# CENTRALE02c3.net
KiCad netlist of a schematic drawn in EAGLE
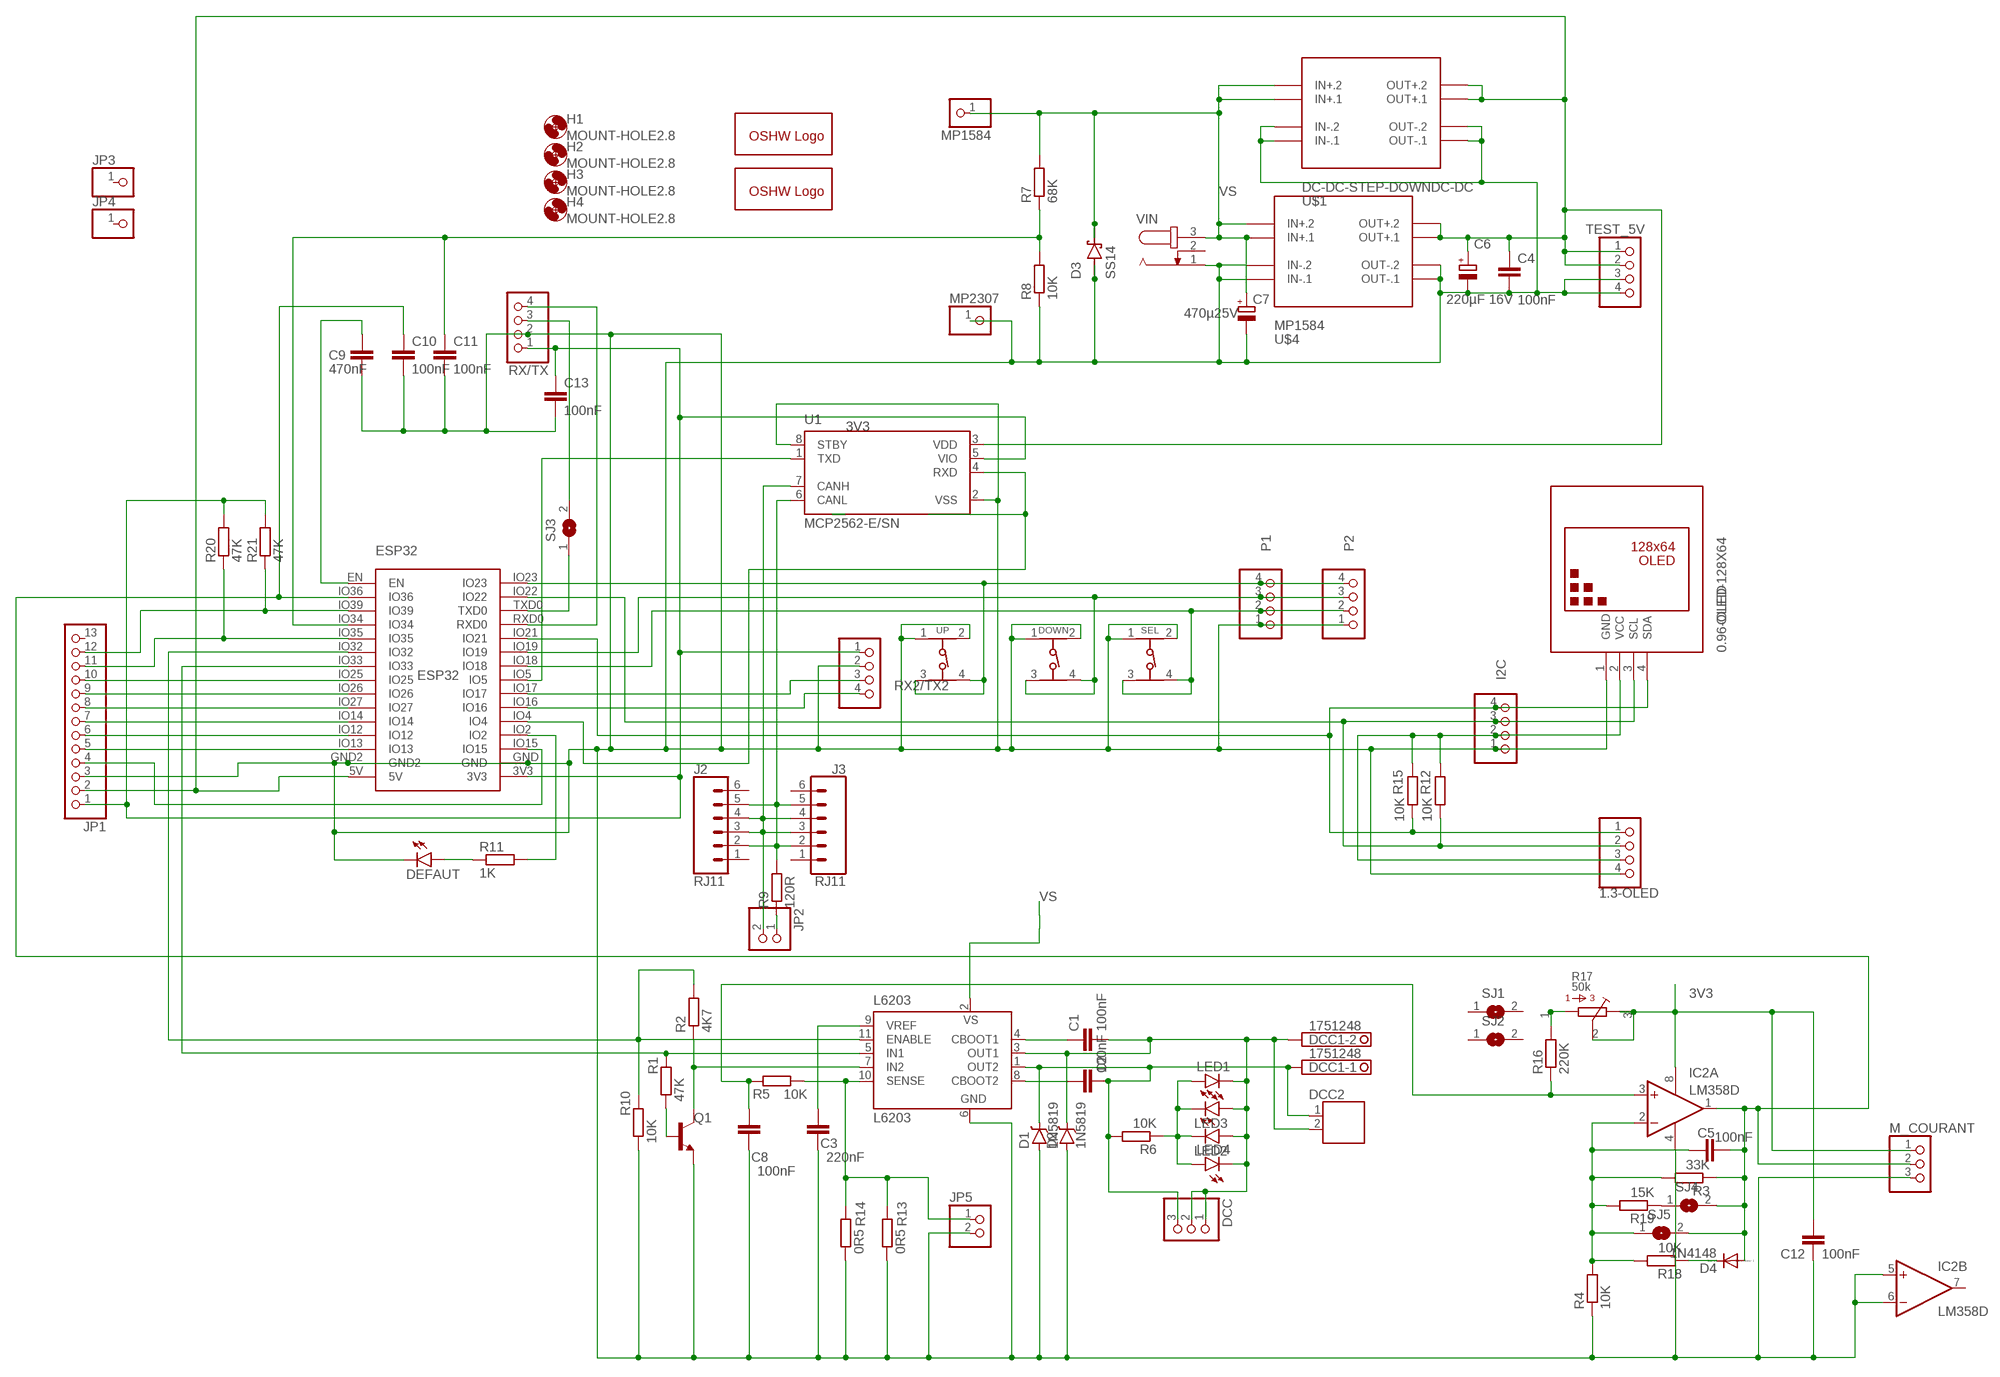
[diagram p0: schematic, sheet 1]

(export (version "E")
  (design (tool "Eeschema 10.0.6"))
  (components
    (comp (ref "0.96-OLED")
      (value "OLED-128X64")
      (footprint "eagle-import:DISPLAY-OLED-128X64-I2C")
      (libsource (lib "eagle-import") (part "DISPLAY-OLED-128X64-I2C"))
    )
    (comp (ref "1.3-OLED")
      (value "PINHD-1X4")
      (footprint "eagle-import:1X04")
      (libsource (lib "eagle-import") (part "PINHD-1X4"))
    )
    (comp (ref "C1")
      (value "100nF")
      (footprint "eagle-import:C1206")
      (libsource (lib "eagle-import") (part "C-EUC1206"))
    )
    (comp (ref "C2")
      (value "100nF")
      (footprint "eagle-import:C1206")
      (libsource (lib "eagle-import") (part "C-EUC1206"))
    )
    (comp (ref "C3")
      (value "220nF")
      (footprint "eagle-import:C1206")
      (libsource (lib "eagle-import") (part "C-EUC1206"))
    )
    (comp (ref "C4")
      (value "100nF")
      (footprint "eagle-import:C1206")
      (libsource (lib "eagle-import") (part "C-EUC1206"))
    )
    (comp (ref "C5")
      (value "100nF")
      (footprint "eagle-import:C1206")
      (libsource (lib "eagle-import") (part "C-EUC1206"))
    )
    (comp (ref "C6")
      (value "220µF 16V")
      (footprint "eagle-import:E2,5-7")
      (libsource (lib "eagle-import") (part "CPOL-EUE2.5-7"))
    )
    (comp (ref "C7")
      (value "470µ25V")
      (footprint "eagle-import:E5-10,5")
      (libsource (lib "eagle-import") (part "CPOL-EUE5-10.5"))
    )
    (comp (ref "C8")
      (value "100nF")
      (footprint "eagle-import:C1206")
      (libsource (lib "eagle-import") (part "C-EUC1206"))
    )
    (comp (ref "C9")
      (value "470nF")
      (footprint "eagle-import:C1206")
      (libsource (lib "eagle-import") (part "C-EUC1206"))
    )
    (comp (ref "C10")
      (value "100nF")
      (footprint "eagle-import:C1206")
      (libsource (lib "eagle-import") (part "C-EUC1206"))
    )
    (comp (ref "C11")
      (value "100nF")
      (footprint "eagle-import:C1206")
      (libsource (lib "eagle-import") (part "C-EUC1206"))
    )
    (comp (ref "C12")
      (value "100nF")
      (footprint "eagle-import:C1206")
      (libsource (lib "eagle-import") (part "C-EUC1206"))
    )
    (comp (ref "C13")
      (value "100nF")
      (footprint "eagle-import:C1206")
      (libsource (lib "eagle-import") (part "C-EUC1206"))
    )
    (comp (ref "D1")
      (value "1N5819")
      (footprint "eagle-import:SMA-DIODE")
      (fields (field (name "MF") "ON Semiconductor") (field (name "MP") "MBRA140"))
      (libsource (lib "eagle-import") (part "MBRA140"))
    )
    (comp (ref "D2")
      (value "1N5819")
      (footprint "eagle-import:SMA-DIODE")
      (fields (field (name "MF") "ON Semiconductor") (field (name "MP") "MBRA140"))
      (libsource (lib "eagle-import") (part "MBRA140"))
    )
    (comp (ref "D3")
      (value "SS14")
      (footprint "eagle-import:DIOM4325X250N")
      (fields (field (name "MF") "Taiwan Semiconductor"))
      (libsource (lib "eagle-import") (part "SS14"))
    )
    (comp (ref "D4")
      (value "1N4148")
      (footprint "eagle-import:DO35-7")
      (libsource (lib "eagle-import") (part "1N4148DO35-7"))
    )
    (comp (ref "DCC")
      (value "PINHD-1X3")
      (footprint "eagle-import:1X03")
      (libsource (lib "eagle-import") (part "PINHD-1X3"))
    )
    (comp (ref "DCC1")
      (value "1751248")
      (footprint "eagle-import:1751248")
      (libsource (lib "eagle-import") (part "1751248"))
    )
    (comp (ref "DCC2")
      (value "691502710002")
      (footprint "eagle-import:691502710002")
      (libsource (lib "eagle-import") (part "691502710002"))
    )
    (comp (ref "DEFAUT")
      (value "LEDSMT1206")
      (footprint "eagle-import:1206")
      (libsource (lib "eagle-import") (part "LEDSMT1206"))
    )
    (comp (ref "DOWN")
      (value "430456073736")
      (footprint "eagle-import:4304X60737X6")
      (libsource (lib "eagle-import") (part "430456073736"))
    )
    (comp (ref "ESP32")
      (value "ESP32")
      (footprint "eagle-import:ESP32")
      (fields (field (name "MF") "Texas Instruments") (field (name "MP") "SN754410"))
      (libsource (lib "eagle-import") (part "ESP32"))
    )
    (comp (ref "GOLD_ORB_SM1")
      (value "OSHWLOGOLOGO5MM")
      (footprint "eagle-import:OSHW_5MM")
      (libsource (lib "eagle-import") (part "OSHWLOGOLOGO5MM"))
    )
    (comp (ref "GOLD_ORB_SM2")
      (value "OSHWLOGOLOGO5MM")
      (footprint "eagle-import:OSHW_5MM")
      (libsource (lib "eagle-import") (part "OSHWLOGOLOGO5MM"))
    )
    (comp (ref "H1")
      (value "MOUNT-HOLE2.8")
      (footprint "eagle-import:2,8")
      (libsource (lib "eagle-import") (part "MOUNT-HOLE2.8"))
    )
    (comp (ref "H2")
      (value "MOUNT-HOLE2.8")
      (footprint "eagle-import:2,8")
      (libsource (lib "eagle-import") (part "MOUNT-HOLE2.8"))
    )
    (comp (ref "H3")
      (value "MOUNT-HOLE2.8")
      (footprint "eagle-import:2,8")
      (libsource (lib "eagle-import") (part "MOUNT-HOLE2.8"))
    )
    (comp (ref "H4")
      (value "MOUNT-HOLE2.8")
      (footprint "eagle-import:2,8")
      (libsource (lib "eagle-import") (part "MOUNT-HOLE2.8"))
    )
    (comp (ref "I2C")
      (value "PINHD-1X4")
      (footprint "eagle-import:1X04")
      (libsource (lib "eagle-import") (part "PINHD-1X4"))
    )
    (comp (ref "IC2")
      (value "LM358D")
      (footprint "eagle-import:SO08")
      (libsource (lib "eagle-import") (part "LM358D"))
    )
    (comp (ref "J2")
      (value "RJ11")
      (footprint "eagle-import:RJ11-6")
      (libsource (lib "eagle-import") (part "RJ11-6"))
    )
    (comp (ref "J3")
      (value "RJ11")
      (footprint "eagle-import:RJ11-6")
      (libsource (lib "eagle-import") (part "RJ11-6"))
    )
    (comp (ref "JP1")
      (value "PINHD-1X13")
      (footprint "eagle-import:1X13")
      (libsource (lib "eagle-import") (part "PINHD-1X13"))
    )
    (comp (ref "JP2")
      (value "PINHD-1X2")
      (footprint "eagle-import:1X02")
      (libsource (lib "eagle-import") (part "PINHD-1X2"))
    )
    (comp (ref "JP3")
      (value "PINHD-1X1")
      (footprint "eagle-import:1X01")
      (libsource (lib "eagle-import") (part "PINHD-1X1"))
    )
    (comp (ref "JP4")
      (value "PINHD-1X1")
      (footprint "eagle-import:1X01")
      (libsource (lib "eagle-import") (part "PINHD-1X1"))
    )
    (comp (ref "JP5")
      (value "PINHD-1X2")
      (footprint "eagle-import:1X02")
      (libsource (lib "eagle-import") (part "PINHD-1X2"))
    )
    (comp (ref "L6203")
      (value "L6203")
      (footprint "eagle-import:MULTIWATT-11")
      (libsource (lib "eagle-import") (part "L6203"))
    )
    (comp (ref "LED1")
      (value "LEDSMT1206")
      (footprint "eagle-import:1206")
      (libsource (lib "eagle-import") (part "LEDSMT1206"))
    )
    (comp (ref "LED2")
      (value "LED3MM")
      (footprint "eagle-import:LED3MM")
      (libsource (lib "eagle-import") (part "LED3MM"))
    )
    (comp (ref "LED3")
      (value "LEDSMT1206")
      (footprint "eagle-import:1206")
      (libsource (lib "eagle-import") (part "LEDSMT1206"))
    )
    (comp (ref "LED4")
      (value "LED3MM")
      (footprint "eagle-import:LED3MM")
      (libsource (lib "eagle-import") (part "LED3MM"))
    )
    (comp (ref "MP1584")
      (value "PINHD-1X1")
      (footprint "eagle-import:1X01")
      (libsource (lib "eagle-import") (part "pinhead_325_PINHD-1X1"))
    )
    (comp (ref "MP2307")
      (value "PINHD-1X1")
      (footprint "eagle-import:1X01")
      (libsource (lib "eagle-import") (part "pinhead_325_PINHD-1X1"))
    )
    (comp (ref "M_COURANT")
      (value "PINHD-1X3")
      (footprint "eagle-import:1X03")
      (libsource (lib "eagle-import") (part "PINHD-1X3"))
    )
    (comp (ref "P1")
      (value "PINHD-1X4")
      (footprint "eagle-import:1X04")
      (libsource (lib "eagle-import") (part "PINHD-1X4"))
    )
    (comp (ref "P2")
      (value "PINHD-1X4")
      (footprint "eagle-import:1X04")
      (libsource (lib "eagle-import") (part "PINHD-1X4"))
    )
    (comp (ref "Q1")
      (value "MMBT3904LT1-NPN-SOT23-BEC")
      (footprint "eagle-import:SOT23-BEC")
      (libsource (lib "eagle-import") (part "-NPN-SOT23-BECMMBT3904LT1"))
    )
    (comp (ref "R1")
      (value "47K")
      (footprint "eagle-import:R0805")
      (libsource (lib "eagle-import") (part "R-EU_R0805"))
    )
    (comp (ref "R2")
      (value "4K7")
      (footprint "eagle-import:R0805")
      (libsource (lib "eagle-import") (part "R-EU_R0805"))
    )
    (comp (ref "R3")
      (value "33K")
      (footprint "eagle-import:R0805")
      (libsource (lib "eagle-import") (part "R-EU_R0805"))
    )
    (comp (ref "R4")
      (value "10K")
      (footprint "eagle-import:R0805")
      (libsource (lib "eagle-import") (part "R-EU_R0805"))
    )
    (comp (ref "R5")
      (value "10K")
      (footprint "eagle-import:R0805")
      (libsource (lib "eagle-import") (part "R-EU_R0805"))
    )
    (comp (ref "R6")
      (value "10K")
      (footprint "eagle-import:R0805")
      (libsource (lib "eagle-import") (part "R-EU_R0805"))
    )
    (comp (ref "R7")
      (value "68K")
      (footprint "eagle-import:R0805")
      (libsource (lib "eagle-import") (part "R-EU_R0805"))
    )
    (comp (ref "R8")
      (value "10K")
      (footprint "eagle-import:R0805")
      (libsource (lib "eagle-import") (part "R-EU_R0805"))
    )
    (comp (ref "R9")
      (value "120R")
      (footprint "eagle-import:M1206")
      (libsource (lib "eagle-import") (part "resistor_348_R-EU_M1206"))
    )
    (comp (ref "R10")
      (value "10K")
      (footprint "eagle-import:R0805")
      (libsource (lib "eagle-import") (part "R-EU_R0805"))
    )
    (comp (ref "R11")
      (value "1K")
      (footprint "eagle-import:R0805")
      (libsource (lib "eagle-import") (part "R-EU_R0805"))
    )
    (comp (ref "R12")
      (value "10K")
      (footprint "eagle-import:R0805")
      (libsource (lib "eagle-import") (part "R-EU_R0805"))
    )
    (comp (ref "R13")
      (value "0R5")
      (footprint "eagle-import:R2512")
      (libsource (lib "eagle-import") (part "R-EU_R2512"))
    )
    (comp (ref "R14")
      (value "0R5")
      (footprint "eagle-import:R2512")
      (libsource (lib "eagle-import") (part "R-EU_R2512"))
    )
    (comp (ref "R15")
      (value "10K")
      (footprint "eagle-import:R0805")
      (libsource (lib "eagle-import") (part "R-EU_R0805"))
    )
    (comp (ref "R16")
      (value "220K")
      (footprint "eagle-import:R0805")
      (libsource (lib "eagle-import") (part "R-EU_R0805"))
    )
    (comp (ref "R17")
      (value "50k")
      (footprint "eagle-import:3386-MULTI")
      (libsource (lib "eagle-import") (part "3386"))
    )
    (comp (ref "R18")
      (value "10K")
      (footprint "eagle-import:R0805")
      (libsource (lib "eagle-import") (part "R-EU_R0805"))
    )
    (comp (ref "R19")
      (value "15K")
      (footprint "eagle-import:R0805")
      (libsource (lib "eagle-import") (part "R-EU_R0805"))
    )
    (comp (ref "R20")
      (value "47K")
      (footprint "eagle-import:R0805")
      (libsource (lib "eagle-import") (part "R-EU_R0805"))
    )
    (comp (ref "R21")
      (value "47K")
      (footprint "eagle-import:R0805")
      (libsource (lib "eagle-import") (part "R-EU_R0805"))
    )
    (comp (ref "RX/TX")
      (value "PINHD-1X4")
      (footprint "eagle-import:1X04")
      (libsource (lib "eagle-import") (part "PINHD-1X4"))
    )
    (comp (ref "RX2/TX2")
      (value "PINHD-1X4")
      (footprint "eagle-import:1X04")
      (libsource (lib "eagle-import") (part "PINHD-1X4"))
    )
    (comp (ref "SEL")
      (value "430456073736")
      (footprint "eagle-import:4304X60737X6")
      (libsource (lib "eagle-import") (part "430456073736"))
    )
    (comp (ref "SJ1") (value "SJ") (footprint "eagle-import:SJ") (libsource (lib "eagle-import") (part "SJ")))
    (comp (ref "SJ2") (value "SJ") (footprint "eagle-import:SJ") (libsource (lib "eagle-import") (part "SJ")))
    (comp (ref "SJ3") (value "SJ") (footprint "eagle-import:SJ") (libsource (lib "eagle-import") (part "SJ")))
    (comp (ref "SJ4") (value "SJ") (footprint "eagle-import:SJ") (libsource (lib "eagle-import") (part "SJ")))
    (comp (ref "SJ5") (value "SJ") (footprint "eagle-import:SJ") (libsource (lib "eagle-import") (part "SJ")))
    (comp (ref "TEST_5V")
      (value "PINHD-1X4")
      (footprint "eagle-import:1X04")
      (libsource (lib "eagle-import") (part "PINHD-1X4"))
    )
    (comp (ref "U$1")
      (value "DC-DC-STEP-DOWNDC-DC")
      (footprint "eagle-import:DC-DC-STEP-DOWN")
      (libsource (lib "eagle-import") (part "DC-DC-STEP-DOWNDC-DC"))
    )
    (comp (ref "U$4")
      (value "MP1584")
      (footprint "eagle-import:DC-DC-STEP-DOWN-MP1584")
      (libsource (lib "eagle-import") (part "DC-DC-STEP-DOWN-MP1584"))
    )
    (comp (ref "U1")
      (value "MCP2562-E/SN")
      (footprint "eagle-import:SOIC127P600X175-8N")
      (fields (field (name "MF") "Microchip"))
      (libsource (lib "eagle-import") (part "MCP2562-E/SN"))
    )
    (comp (ref "UP")
      (value "430456073736")
      (footprint "eagle-import:4304X60737X6")
      (libsource (lib "eagle-import") (part "430456073736"))
    )
    (comp (ref "VIN")
      (value "JACK-PLUG0")
      (footprint "eagle-import:SPC4077")
      (libsource (lib "eagle-import") (part "JACK-PLUG0"))
    )
  )
  (nets
    (net (code "1") (name "/3V3") (class "Default")
      (node (ref "0.96-OLED") (pin "2") (pinfunction "VCC_2") (pintype "power_in"))
      (node (ref "1.3-OLED") (pin "3") (pinfunction "3_3") (pintype "passive"))
      (node (ref "C12") (pin "2") (pinfunction "2_2") (pintype "passive"))
      (node (ref "C13") (pin "2") (pinfunction "2_2") (pintype "passive"))
      (node (ref "ESP32") (pin "3V3") (pinfunction "3V3_3V3") (pintype "power_in"))
      (node (ref "I2C") (pin "2") (pinfunction "2_2") (pintype "passive"))
      (node (ref "IC2") (pin "8") (pinfunction "V+_8") (pintype "power_in"))
      (node (ref "JP1") (pin "1") (pinfunction "1_1") (pintype "passive"))
      (node (ref "M_COURANT") (pin "1") (pinfunction "1_1") (pintype "passive"))
      (node (ref "R12") (pin "1") (pinfunction "1_1") (pintype "passive"))
      (node (ref "R15") (pin "1") (pinfunction "1_1") (pintype "passive"))
      (node (ref "R17") (pin "2") (pinfunction "2_2") (pintype "passive"))
      (node (ref "R17") (pin "3") (pinfunction "3_3") (pintype "passive"))
      (node (ref "R17") (pin "6") (pinfunction "6_6") (pintype "passive"))
      (node (ref "R20") (pin "2") (pinfunction "2_2") (pintype "passive"))
      (node (ref "R21") (pin "2") (pinfunction "2_2") (pintype "passive"))
      (node (ref "RX/TX") (pin "1") (pinfunction "1_1") (pintype "passive"))
      (node (ref "RX2/TX2") (pin "1") (pinfunction "1_1") (pintype "passive"))
      (node (ref "U1") (pin "5") (pinfunction "VIO_5") (pintype "power_in"))
    )
    (net (code "2") (name "/VS") (class "Default")
      (node (ref "C7") (pin "+") (pinfunction "+_+") (pintype "passive"))
      (node (ref "D3") (pin "C") (pinfunction "K_C") (pintype "passive"))
      (node (ref "L6203") (pin "2") (pinfunction "VS_2") (pintype "power_in"))
      (node (ref "MP1584") (pin "1") (pinfunction "1_1") (pintype "passive"))
      (node (ref "R7") (pin "2") (pinfunction "2_2") (pintype "passive"))
      (node (ref "U$1") (pin "IN+.1") (pinfunction "IN+.1_IN+.1") (pintype "bidirectional"))
      (node (ref "U$1") (pin "IN+.2") (pinfunction "IN+.2_IN+.2") (pintype "bidirectional"))
      (node (ref "U$4") (pin "IN+.1") (pinfunction "IN+.1_IN+.1") (pintype "bidirectional"))
      (node (ref "U$4") (pin "IN+.2") (pinfunction "IN+.2_IN+.2") (pintype "bidirectional"))
      (node (ref "VIN") (pin "3") (pinfunction "3_3") (pintype "passive"))
    )
    (net (code "3") (name "Net-(0.96-OLED-GND)") (class "Default")
      (node (ref "0.96-OLED") (pin "1") (pinfunction "GND_1") (pintype "power_in"))
      (node (ref "1.3-OLED") (pin "4") (pinfunction "4_4") (pintype "passive"))
      (node (ref "C10") (pin "1") (pinfunction "1_1") (pintype "passive"))
      (node (ref "C11") (pin "1") (pinfunction "1_1") (pintype "passive"))
      (node (ref "C12") (pin "1") (pinfunction "1_1") (pintype "passive"))
      (node (ref "C13") (pin "1") (pinfunction "1_1") (pintype "passive"))
      (node (ref "C3") (pin "1") (pinfunction "1_1") (pintype "passive"))
      (node (ref "C4") (pin "2") (pinfunction "2_2") (pintype "passive"))
      (node (ref "C6") (pin "-") (pinfunction "-_-") (pintype "passive"))
      (node (ref "C7") (pin "-") (pinfunction "-_-") (pintype "passive"))
      (node (ref "C8") (pin "1") (pinfunction "1_1") (pintype "passive"))
      (node (ref "C9") (pin "2") (pinfunction "2_2") (pintype "passive"))
      (node (ref "D1") (pin "A") (pinfunction "A_A") (pintype "passive"))
      (node (ref "D2") (pin "A") (pinfunction "A_A") (pintype "passive"))
      (node (ref "D3") (pin "A") (pinfunction "A_A") (pintype "passive"))
      (node (ref "DEFAUT") (pin "C") (pinfunction "C_C") (pintype "passive"))
      (node (ref "DOWN") (pin "1") (pinfunction "1_1") (pintype "passive"))
      (node (ref "DOWN") (pin "2") (pinfunction "3_2") (pintype "passive"))
      (node (ref "ESP32") (pin "GND") (pinfunction "GND_GND") (pintype "power_in"))
      (node (ref "ESP32") (pin "GND2") (pinfunction "GND2_GND2") (pintype "power_in"))
      (node (ref "I2C") (pin "1") (pinfunction "1_1") (pintype "passive"))
      (node (ref "IC2") (pin "4") (pinfunction "V-_4") (pintype "power_in"))
      (node (ref "IC2") (pin "5") (pinfunction "+IN_5") (pintype "input"))
      (node (ref "IC2") (pin "6") (pinfunction "-IN_6") (pintype "input"))
      (node (ref "JP1") (pin "3") (pinfunction "3_3") (pintype "passive"))
      (node (ref "JP5") (pin "2") (pinfunction "2_2") (pintype "passive"))
      (node (ref "L6203") (pin "6") (pinfunction "GND_6") (pintype "power_in"))
      (node (ref "MP2307") (pin "1") (pinfunction "1_1") (pintype "passive"))
      (node (ref "M_COURANT") (pin "3") (pinfunction "3_3") (pintype "passive"))
      (node (ref "P1") (pin "1") (pinfunction "1_1") (pintype "passive"))
      (node (ref "P2") (pin "1") (pinfunction "1_1") (pintype "passive"))
      (node (ref "Q1") (pin "E") (pinfunction "E_E") (pintype "passive"))
      (node (ref "R10") (pin "1") (pinfunction "1_1") (pintype "passive"))
      (node (ref "R13") (pin "1") (pinfunction "1_1") (pintype "passive"))
      (node (ref "R14") (pin "1") (pinfunction "1_1") (pintype "passive"))
      (node (ref "R4") (pin "1") (pinfunction "1_1") (pintype "passive"))
      (node (ref "R8") (pin "1") (pinfunction "1_1") (pintype "passive"))
      (node (ref "RX/TX") (pin "2") (pinfunction "2_2") (pintype "passive"))
      (node (ref "RX2/TX2") (pin "2") (pinfunction "2_2") (pintype "passive"))
      (node (ref "SEL") (pin "1") (pinfunction "1_1") (pintype "passive"))
      (node (ref "SEL") (pin "2") (pinfunction "3_2") (pintype "passive"))
      (node (ref "TEST_5V") (pin "3") (pinfunction "3_3") (pintype "passive"))
      (node (ref "TEST_5V") (pin "4") (pinfunction "4_4") (pintype "passive"))
      (node (ref "U$1") (pin "IN-.1") (pinfunction "IN-.1_IN-.1") (pintype "bidirectional"))
      (node (ref "U$1") (pin "IN-.2") (pinfunction "IN-.2_IN-.2") (pintype "bidirectional"))
      (node (ref "U$1") (pin "OUT-.1") (pinfunction "OUT-.1_OUT-.1") (pintype "bidirectional"))
      (node (ref "U$1") (pin "OUT-.2") (pinfunction "OUT-.2_OUT-.2") (pintype "bidirectional"))
      (node (ref "U$4") (pin "IN-.1") (pinfunction "IN-.1_IN-.1") (pintype "bidirectional"))
      (node (ref "U$4") (pin "IN-.2") (pinfunction "IN-.2_IN-.2") (pintype "bidirectional"))
      (node (ref "U$4") (pin "OUT-.1") (pinfunction "OUT-.1_OUT-.1") (pintype "bidirectional"))
      (node (ref "U$4") (pin "OUT-.2") (pinfunction "OUT-.2_OUT-.2") (pintype "bidirectional"))
      (node (ref "U1") (pin "2") (pinfunction "VSS_2") (pintype "power_in"))
      (node (ref "U1") (pin "8") (pinfunction "STBY_8") (pintype "input"))
      (node (ref "UP") (pin "1") (pinfunction "1_1") (pintype "passive"))
      (node (ref "UP") (pin "2") (pinfunction "3_2") (pintype "passive"))
      (node (ref "VIN") (pin "1") (pinfunction "1_1") (pintype "passive"))
    )
    (net (code "4") (name "Net-(0.96-OLED-SCL)") (class "Default")
      (node (ref "0.96-OLED") (pin "3") (pinfunction "SCL_3") (pintype "bidirectional"))
      (node (ref "1.3-OLED") (pin "2") (pinfunction "2_2") (pintype "passive"))
      (node (ref "ESP32") (pin "IO22") (pinfunction "IO22_IO22") (pintype "bidirectional"))
      (node (ref "I2C") (pin "3") (pinfunction "3_3") (pintype "passive"))
      (node (ref "R12") (pin "2") (pinfunction "2_2") (pintype "passive"))
    )
    (net (code "5") (name "Net-(0.96-OLED-SDA)") (class "Default")
      (node (ref "0.96-OLED") (pin "4") (pinfunction "SDA_4") (pintype "bidirectional"))
      (node (ref "1.3-OLED") (pin "1") (pinfunction "1_1") (pintype "passive"))
      (node (ref "ESP32") (pin "IO21") (pinfunction "IO21_IO21") (pintype "bidirectional"))
      (node (ref "I2C") (pin "4") (pinfunction "4_4") (pintype "passive"))
      (node (ref "R15") (pin "2") (pinfunction "2_2") (pintype "passive"))
    )
    (net (code "6") (name "Net-(C9-Pad1)") (class "Default")
      (node (ref "C9") (pin "1") (pinfunction "1_1") (pintype "passive"))
      (node (ref "ESP32") (pin "EN") (pinfunction "EN_EN") (pintype "bidirectional"))
    )
    (net (code "7") (name "Net-(C11-Pad2)") (class "Default")
      (node (ref "C11") (pin "2") (pinfunction "2_2") (pintype "passive"))
      (node (ref "ESP32") (pin "IO34") (pinfunction "IO34_IO34") (pintype "bidirectional"))
      (node (ref "R7") (pin "1") (pinfunction "1_1") (pintype "passive"))
      (node (ref "R8") (pin "2") (pinfunction "2_2") (pintype "passive"))
    )
    (net (code "8") (name "Net-(D4-PadC)") (class "Default")
      (node (ref "D4") (pin "C") (pinfunction "C_C") (pintype "passive"))
      (node (ref "R18") (pin "1") (pinfunction "1_1") (pintype "passive"))
    )
    (net (code "9") (name "Net-(DCC1A-K)") (class "Default")
      (node (ref "C2") (pin "2") (pinfunction "2_2") (pintype "passive"))
      (node (ref "D1") (pin "C") (pinfunction "C_C") (pintype "passive"))
      (node (ref "DCC") (pin "3") (pinfunction "3_3") (pintype "passive"))
      (node (ref "DCC1") (pin "1") (pinfunction "K_1") (pintype "passive"))
      (node (ref "DCC2") (pin "1") (pinfunction "1_1") (pintype "passive"))
      (node (ref "L6203") (pin "1") (pinfunction "OUT2_1") (pintype "output"))
      (node (ref "R6") (pin "2") (pinfunction "2_2") (pintype "passive"))
    )
    (net (code "10") (name "Net-(DCC1B-K)") (class "Default")
      (node (ref "C1") (pin "2") (pinfunction "2_2") (pintype "passive"))
      (node (ref "D2") (pin "C") (pinfunction "C_C") (pintype "passive"))
      (node (ref "DCC") (pin "1") (pinfunction "1_1") (pintype "passive"))
      (node (ref "DCC") (pin "2") (pinfunction "2_2") (pintype "passive"))
      (node (ref "DCC1") (pin "2") (pinfunction "K_2") (pintype "passive"))
      (node (ref "DCC2") (pin "2") (pinfunction "2_2") (pintype "passive"))
      (node (ref "L6203") (pin "3") (pinfunction "OUT1_3") (pintype "output"))
      (node (ref "LED1") (pin "C") (pinfunction "C_C") (pintype "passive"))
      (node (ref "LED2") (pin "A") (pinfunction "A_A") (pintype "passive"))
      (node (ref "LED3") (pin "A") (pinfunction "A_A") (pintype "passive"))
      (node (ref "LED4") (pin "K") (pinfunction "C_K") (pintype "passive"))
    )
    (net (code "11") (name "Net-(DEFAUT-PadA)") (class "Default")
      (node (ref "DEFAUT") (pin "A") (pinfunction "A_A") (pintype "passive"))
      (node (ref "R11") (pin "1") (pinfunction "1_1") (pintype "passive"))
    )
    (net (code "12") (name "Net-(DOWN-2)") (class "Default")
      (node (ref "DOWN") (pin "3") (pinfunction "2_3") (pintype "passive"))
      (node (ref "DOWN") (pin "4") (pinfunction "4_4") (pintype "passive"))
      (node (ref "ESP32") (pin "IO19") (pinfunction "IO19_IO19") (pintype "bidirectional"))
      (node (ref "P1") (pin "3") (pinfunction "3_3") (pintype "passive"))
      (node (ref "P2") (pin "3") (pinfunction "3_3") (pintype "passive"))
    )
    (net (code "13") (name "Net-(ESP32-PadIO2)") (class "Default")
      (node (ref "ESP32") (pin "IO2") (pinfunction "IO2_IO2") (pintype "bidirectional"))
      (node (ref "R11") (pin "2") (pinfunction "2_2") (pintype "passive"))
    )
    (net (code "14") (name "Net-(ESP32-PadIO12)") (class "Default")
      (node (ref "ESP32") (pin "IO12") (pinfunction "IO12_IO12") (pintype "bidirectional"))
      (node (ref "JP1") (pin "6") (pinfunction "6_6") (pintype "passive"))
    )
    (net (code "15") (name "Net-(ESP32-PadIO13)") (class "Default")
      (node (ref "ESP32") (pin "IO13") (pinfunction "IO13_IO13") (pintype "bidirectional"))
      (node (ref "JP1") (pin "5") (pinfunction "5_5") (pintype "passive"))
    )
    (net (code "16") (name "Net-(ESP32-PadIO14)") (class "Default")
      (node (ref "ESP32") (pin "IO14") (pinfunction "IO14_IO14") (pintype "bidirectional"))
      (node (ref "JP1") (pin "7") (pinfunction "7_7") (pintype "passive"))
    )
    (net (code "17") (name "Net-(ESP32-PadIO15)") (class "Default")
      (node (ref "ESP32") (pin "IO15") (pinfunction "IO15_IO15") (pintype "bidirectional"))
      (node (ref "JP1") (pin "4") (pinfunction "4_4") (pintype "passive"))
    )
    (net (code "18") (name "Net-(ESP32-PadIO16)") (class "Default")
      (node (ref "ESP32") (pin "IO16") (pinfunction "IO16_IO16") (pintype "bidirectional"))
      (node (ref "RX2/TX2") (pin "4") (pinfunction "4_4") (pintype "passive"))
    )
    (net (code "19") (name "Net-(ESP32-PadIO17)") (class "Default")
      (node (ref "ESP32") (pin "IO17") (pinfunction "IO17_IO17") (pintype "bidirectional"))
      (node (ref "RX2/TX2") (pin "3") (pinfunction "3_3") (pintype "passive"))
    )
    (net (code "20") (name "Net-(ESP32-PadIO25)") (class "Default")
      (node (ref "ESP32") (pin "IO25") (pinfunction "IO25_IO25") (pintype "bidirectional"))
      (node (ref "JP1") (pin "10") (pinfunction "10_10") (pintype "passive"))
    )
    (net (code "21") (name "Net-(ESP32-PadIO26)") (class "Default")
      (node (ref "ESP32") (pin "IO26") (pinfunction "IO26_IO26") (pintype "bidirectional"))
      (node (ref "JP1") (pin "9") (pinfunction "9_9") (pintype "passive"))
    )
    (net (code "22") (name "Net-(ESP32-PadIO27)") (class "Default")
      (node (ref "ESP32") (pin "IO27") (pinfunction "IO27_IO27") (pintype "bidirectional"))
      (node (ref "JP1") (pin "8") (pinfunction "8_8") (pintype "passive"))
    )
    (net (code "23") (name "Net-(ESP32-PadIO35)") (class "Default")
      (node (ref "ESP32") (pin "IO35") (pinfunction "IO35_IO35") (pintype "bidirectional"))
      (node (ref "JP1") (pin "11") (pinfunction "11_11") (pintype "passive"))
      (node (ref "R20") (pin "1") (pinfunction "1_1") (pintype "passive"))
    )
    (net (code "24") (name "Net-(ESP32-PadIO39)") (class "Default")
      (node (ref "ESP32") (pin "IO39") (pinfunction "IO39_IO39") (pintype "bidirectional"))
      (node (ref "JP1") (pin "12") (pinfunction "12_12") (pintype "passive"))
      (node (ref "R21") (pin "1") (pinfunction "1_1") (pintype "passive"))
    )
    (net (code "25") (name "Net-(ESP32-PadRXD0)") (class "Default")
      (node (ref "ESP32") (pin "RXD0") (pinfunction "RXD0_RXD0") (pintype "bidirectional"))
      (node (ref "RX/TX") (pin "4") (pinfunction "4_4") (pintype "passive"))
    )
    (net (code "26") (name "Net-(ESP32-PadTXD0)") (class "Default")
      (node (ref "ESP32") (pin "TXD0") (pinfunction "TXD0_TXD0") (pintype "bidirectional"))
      (node (ref "SJ3") (pin "1") (pinfunction "1_1") (pintype "passive"))
    )
    (net (code "27") (name "Net-(IC2A-+IN)") (class "Default")
      (node (ref "C8") (pin "2") (pinfunction "2_2") (pintype "passive"))
      (node (ref "IC2") (pin "3") (pinfunction "+IN_3") (pintype "input"))
      (node (ref "R16") (pin "1") (pinfunction "1_1") (pintype "passive"))
      (node (ref "R5") (pin "2") (pinfunction "2_2") (pintype "passive"))
    )
    (net (code "28") (name "Net-(IC2A--IN)") (class "Default")
      (node (ref "C5") (pin "1") (pinfunction "1_1") (pintype "passive"))
      (node (ref "IC2") (pin "2") (pinfunction "-IN_2") (pintype "input"))
      (node (ref "R18") (pin "2") (pinfunction "2_2") (pintype "passive"))
      (node (ref "R19") (pin "2") (pinfunction "2_2") (pintype "passive"))
      (node (ref "R3") (pin "2") (pinfunction "2_2") (pintype "passive"))
      (node (ref "R4") (pin "2") (pinfunction "2_2") (pintype "passive"))
      (node (ref "SJ5") (pin "1") (pinfunction "1_1") (pintype "passive"))
    )
    (net (code "29") (name "Net-(IC2A-OUT)") (class "Default")
      (node (ref "C10") (pin "2") (pinfunction "2_2") (pintype "passive"))
      (node (ref "C5") (pin "2") (pinfunction "2_2") (pintype "passive"))
      (node (ref "D4") (pin "A") (pinfunction "A_A") (pintype "passive"))
      (node (ref "ESP32") (pin "IO36") (pinfunction "IO36_IO36") (pintype "bidirectional"))
      (node (ref "IC2") (pin "1") (pinfunction "OUT_1") (pintype "output"))
      (node (ref "M_COURANT") (pin "2") (pinfunction "2_2") (pintype "passive"))
      (node (ref "R3") (pin "1") (pinfunction "1_1") (pintype "passive"))
      (node (ref "SJ4") (pin "2") (pinfunction "2_2") (pintype "passive"))
      (node (ref "SJ5") (pin "2") (pinfunction "2_2") (pintype "passive"))
    )
    (net (code "30") (name "Net-(JP2-Pad1)") (class "Default")
      (node (ref "JP2") (pin "1") (pinfunction "1_1") (pintype "passive"))
      (node (ref "R9") (pin "1") (pinfunction "1_1") (pintype "passive"))
    )
    (net (code "31") (name "Net-(L6203-CBOOT1)") (class "Default")
      (node (ref "C1") (pin "1") (pinfunction "1_1") (pintype "passive"))
      (node (ref "L6203") (pin "4") (pinfunction "CBOOT1_4") (pintype "input"))
    )
    (net (code "32") (name "Net-(L6203-CBOOT2)") (class "Default")
      (node (ref "C2") (pin "1") (pinfunction "1_1") (pintype "passive"))
      (node (ref "L6203") (pin "8") (pinfunction "CBOOT2_8") (pintype "input"))
    )
    (net (code "33") (name "Net-(L6203-ENABLE)") (class "Default")
      (node (ref "ESP32") (pin "IO32") (pinfunction "IO32_IO32") (pintype "bidirectional"))
      (node (ref "L6203") (pin "11") (pinfunction "ENABLE_11") (pintype "input"))
      (node (ref "R10") (pin "2") (pinfunction "2_2") (pintype "passive"))
      (node (ref "R2") (pin "2") (pinfunction "2_2") (pintype "passive"))
    )
    (net (code "34") (name "Net-(L6203-IN1)") (class "Default")
      (node (ref "ESP32") (pin "IO33") (pinfunction "IO33_IO33") (pintype "bidirectional"))
      (node (ref "L6203") (pin "5") (pinfunction "IN1_5") (pintype "input"))
      (node (ref "R1") (pin "2") (pinfunction "2_2") (pintype "passive"))
    )
    (net (code "35") (name "Net-(L6203-IN2)") (class "Default")
      (node (ref "L6203") (pin "7") (pinfunction "IN2_7") (pintype "input"))
      (node (ref "Q1") (pin "C") (pinfunction "C_C") (pintype "passive"))
      (node (ref "R2") (pin "1") (pinfunction "1_1") (pintype "passive"))
    )
    (net (code "36") (name "Net-(L6203-SENSE)") (class "Default")
      (node (ref "JP5") (pin "1") (pinfunction "1_1") (pintype "passive"))
      (node (ref "L6203") (pin "10") (pinfunction "SENSE_10") (pintype "input"))
      (node (ref "R13") (pin "2") (pinfunction "2_2") (pintype "passive"))
      (node (ref "R14") (pin "2") (pinfunction "2_2") (pintype "passive"))
      (node (ref "R5") (pin "1") (pinfunction "1_1") (pintype "passive"))
    )
    (net (code "37") (name "Net-(L6203-VREF)") (class "Default")
      (node (ref "C3") (pin "2") (pinfunction "2_2") (pintype "passive"))
      (node (ref "L6203") (pin "9") (pinfunction "VREF_9") (pintype "input"))
    )
    (net (code "38") (name "Net-(LED2-C)") (class "Default")
      (node (ref "LED1") (pin "A") (pinfunction "A_A") (pintype "passive"))
      (node (ref "LED2") (pin "K") (pinfunction "C_K") (pintype "passive"))
      (node (ref "LED3") (pin "C") (pinfunction "C_C") (pintype "passive"))
      (node (ref "LED4") (pin "A") (pinfunction "A_A") (pintype "passive"))
      (node (ref "R6") (pin "1") (pinfunction "1_1") (pintype "passive"))
    )
    (net (code "39") (name "Net-(Q1-PadB)") (class "Default")
      (node (ref "Q1") (pin "B") (pinfunction "B_B") (pintype "passive"))
      (node (ref "R1") (pin "1") (pinfunction "1_1") (pintype "passive"))
    )
    (net (code "40") (name "Net-(R16-Pad2)") (class "Default")
      (node (ref "R16") (pin "2") (pinfunction "2_2") (pintype "passive"))
      (node (ref "R17") (pin "1") (pinfunction "1_1") (pintype "passive"))
      (node (ref "R17") (pin "4") (pinfunction "4_4") (pintype "passive"))
    )
    (net (code "41") (name "Net-(R19-Pad1)") (class "Default")
      (node (ref "R19") (pin "1") (pinfunction "1_1") (pintype "passive"))
      (node (ref "SJ4") (pin "1") (pinfunction "1_1") (pintype "passive"))
    )
    (net (code "42") (name "Net-(RX/TX-Pad3)") (class "Default")
      (node (ref "RX/TX") (pin "3") (pinfunction "3_3") (pintype "passive"))
      (node (ref "SJ3") (pin "2") (pinfunction "2_2") (pintype "passive"))
    )
    (net (code "43") (name "Net-(SEL-2)") (class "Default")
      (node (ref "ESP32") (pin "IO18") (pinfunction "IO18_IO18") (pintype "bidirectional"))
      (node (ref "P1") (pin "2") (pinfunction "2_2") (pintype "passive"))
      (node (ref "P2") (pin "2") (pinfunction "2_2") (pintype "passive"))
      (node (ref "SEL") (pin "3") (pinfunction "2_3") (pintype "passive"))
      (node (ref "SEL") (pin "4") (pinfunction "4_4") (pintype "passive"))
    )
    (net (code "44") (name "Net-(U1-CANH)") (class "Default")
      (node (ref "J2") (pin "3") (pinfunction "3_3") (pintype "passive"))
      (node (ref "J2") (pin "4") (pinfunction "4_4") (pintype "passive"))
      (node (ref "J3") (pin "3") (pinfunction "3_3") (pintype "passive"))
      (node (ref "J3") (pin "4") (pinfunction "4_4") (pintype "passive"))
      (node (ref "JP2") (pin "2") (pinfunction "2_2") (pintype "passive"))
      (node (ref "U1") (pin "7") (pinfunction "CANH_7") (pintype "input"))
    )
    (net (code "45") (name "Net-(U1-CANL)") (class "Default")
      (node (ref "J2") (pin "2") (pinfunction "2_2") (pintype "passive"))
      (node (ref "J2") (pin "5") (pinfunction "5_5") (pintype "passive"))
      (node (ref "J3") (pin "2") (pinfunction "2_2") (pintype "passive"))
      (node (ref "J3") (pin "5") (pinfunction "5_5") (pintype "passive"))
      (node (ref "R9") (pin "2") (pinfunction "2_2") (pintype "passive"))
      (node (ref "U1") (pin "6") (pinfunction "CANL_6") (pintype "input"))
    )
    (net (code "46") (name "Net-(U1-RXD)") (class "Default")
      (node (ref "ESP32") (pin "IO4") (pinfunction "IO4_IO4") (pintype "bidirectional"))
      (node (ref "U1") (pin "4") (pinfunction "RXD_4") (pintype "output"))
    )
    (net (code "47") (name "Net-(U1-TXD)") (class "Default")
      (node (ref "ESP32") (pin "IO5") (pinfunction "IO5_IO5") (pintype "bidirectional"))
      (node (ref "U1") (pin "1") (pinfunction "TXD_1") (pintype "input"))
    )
    (net (code "48") (name "Net-(U1-VDD)") (class "Default")
      (node (ref "C4") (pin "1") (pinfunction "1_1") (pintype "passive"))
      (node (ref "C6") (pin "+") (pinfunction "+_+") (pintype "passive"))
      (node (ref "ESP32") (pin "5V") (pinfunction "5V_5V") (pintype "power_in"))
      (node (ref "JP1") (pin "2") (pinfunction "2_2") (pintype "passive"))
      (node (ref "TEST_5V") (pin "1") (pinfunction "1_1") (pintype "passive"))
      (node (ref "TEST_5V") (pin "2") (pinfunction "2_2") (pintype "passive"))
      (node (ref "U$1") (pin "OUT+.1") (pinfunction "OUT+.1_OUT+.1") (pintype "bidirectional"))
      (node (ref "U$1") (pin "OUT+.2") (pinfunction "OUT+.2_OUT+.2") (pintype "bidirectional"))
      (node (ref "U$4") (pin "OUT+.1") (pinfunction "OUT+.1_OUT+.1") (pintype "bidirectional"))
      (node (ref "U$4") (pin "OUT+.2") (pinfunction "OUT+.2_OUT+.2") (pintype "bidirectional"))
      (node (ref "U1") (pin "3") (pinfunction "VDD_3") (pintype "power_in"))
    )
    (net (code "49") (name "Net-(UP-2)") (class "Default")
      (node (ref "ESP32") (pin "IO23") (pinfunction "IO23_IO23") (pintype "bidirectional"))
      (node (ref "P1") (pin "4") (pinfunction "4_4") (pintype "passive"))
      (node (ref "P2") (pin "4") (pinfunction "4_4") (pintype "passive"))
      (node (ref "UP") (pin "3") (pinfunction "2_3") (pintype "passive"))
      (node (ref "UP") (pin "4") (pinfunction "4_4") (pintype "passive"))
    )
    (net (code "50") (name "unconnected-(IC2B-OUT-Pad7)") (class "Default")
      (node (ref "IC2") (pin "7") (pinfunction "OUT_7") (pintype "output"))
    )
    (net (code "51") (name "unconnected-(J2-Pad1)") (class "Default")
      (node (ref "J2") (pin "1") (pinfunction "1_1") (pintype "passive"))
    )
    (net (code "52") (name "unconnected-(J2-Pad6)") (class "Default")
      (node (ref "J2") (pin "6") (pinfunction "6_6") (pintype "passive"))
    )
    (net (code "53") (name "unconnected-(J3-Pad1)") (class "Default")
      (node (ref "J3") (pin "1") (pinfunction "1_1") (pintype "passive"))
    )
    (net (code "54") (name "unconnected-(J3-Pad6)") (class "Default")
      (node (ref "J3") (pin "6") (pinfunction "6_6") (pintype "passive"))
    )
    (net (code "55") (name "unconnected-(JP1-Pad13)") (class "Default")
      (node (ref "JP1") (pin "13") (pinfunction "13_13") (pintype "passive"))
    )
    (net (code "56") (name "unconnected-(JP3-Pad1)") (class "Default")
      (node (ref "JP3") (pin "1") (pinfunction "1_1") (pintype "passive"))
    )
    (net (code "57") (name "unconnected-(JP4-Pad1)") (class "Default")
      (node (ref "JP4") (pin "1") (pinfunction "1_1") (pintype "passive"))
    )
    (net (code "58") (name "unconnected-(R17-Pad5)") (class "Default")
      (node (ref "R17") (pin "5") (pinfunction "5_5") (pintype "passive"))
    )
    (net (code "59") (name "unconnected-(SJ1-Pad1)") (class "Default")
      (node (ref "SJ1") (pin "1") (pinfunction "1_1") (pintype "passive"))
    )
    (net (code "60") (name "unconnected-(SJ1-Pad2)") (class "Default")
      (node (ref "SJ1") (pin "2") (pinfunction "2_2") (pintype "passive"))
    )
    (net (code "61") (name "unconnected-(SJ2-Pad1)") (class "Default")
      (node (ref "SJ2") (pin "1") (pinfunction "1_1") (pintype "passive"))
    )
    (net (code "62") (name "unconnected-(SJ2-Pad2)") (class "Default")
      (node (ref "SJ2") (pin "2") (pinfunction "2_2") (pintype "passive"))
    )
    (net (code "63") (name "unconnected-(VIN-Pad2)") (class "Default")
      (node (ref "VIN") (pin "2") (pinfunction "2_2") (pintype "passive"))
    )
  )
)
